# Output_Register.net
KiCad netlist of a schematic drawn in Altium Designer
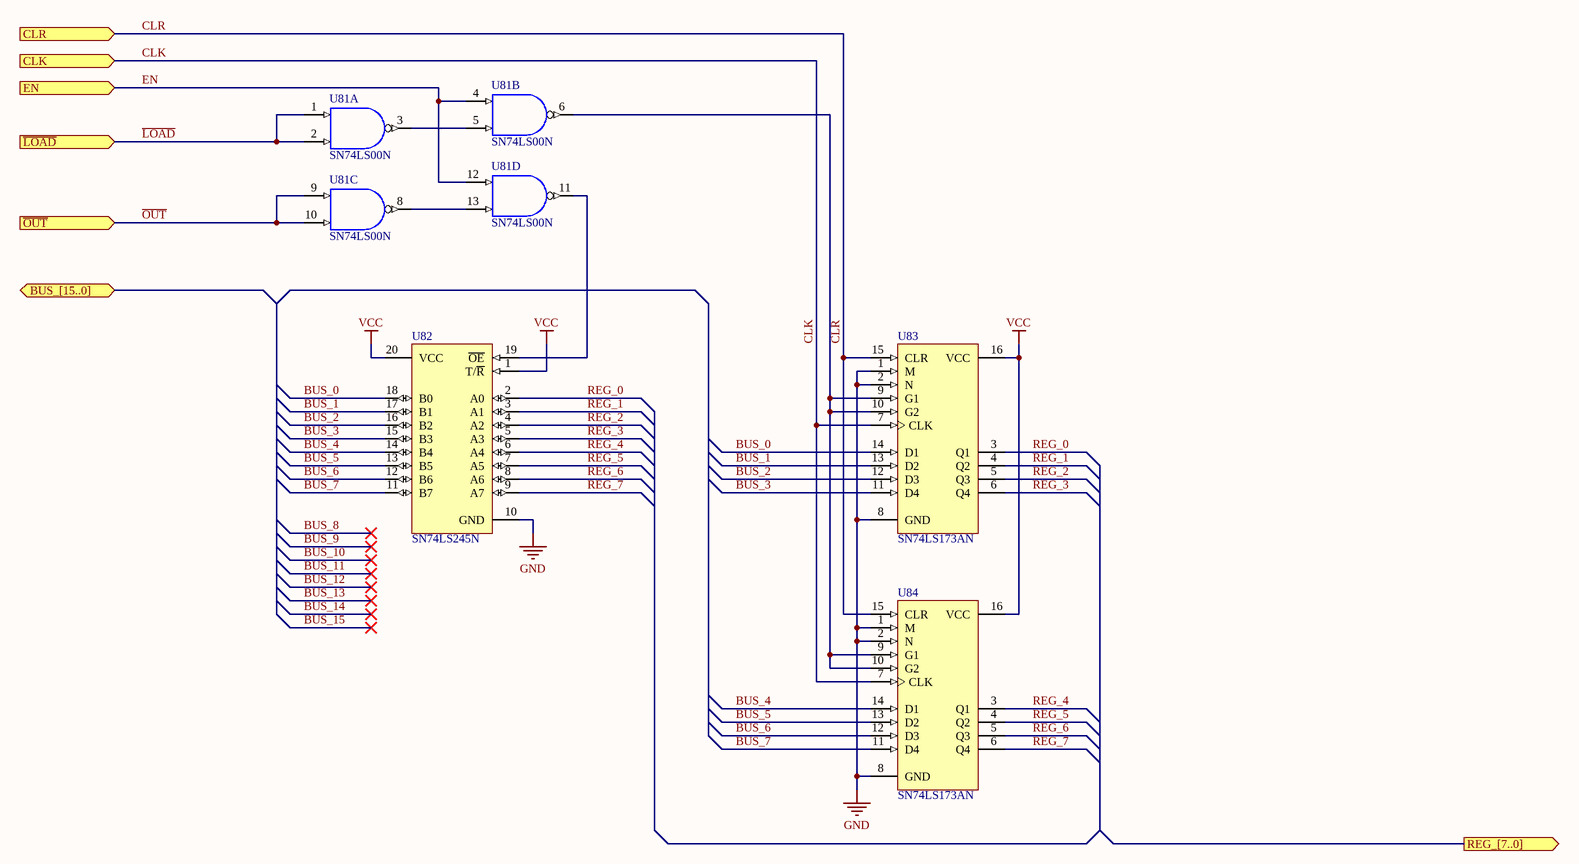
[diagram p0: Output_Register.SchDoc]

(export (version "E")
  (design (tool "Eeschema 10.0.6"))
  (components
    (comp (ref "U81")
      (value "SN74LS00N")
      (footprint "N014")
      (description "Quadruple 2-Input Positive-NAND Gate")
      (fields (field (name "PUBLISHER") "Altium Limited"))
      (libsource (lib "TI Logic Gate 2") (part "SN74LS00N"))
    )
    (comp (ref "U82")
      (value "SN74LS245N")
      (footprint "N020")
      (description "Octal Bus Transceiver with 3-State Outputs")
      (fields (field (name "PUBLISHER") "Altium Limited"))
      (libsource (lib "TI Interface 8-Bit Line Transceiver") (part "SN74LS245N"))
    )
    (comp (ref "U83")
      (value "SN74LS173AN")
      (footprint "N016D")
      (description "4-Bit D-Type Register with 3-State Outputs")
      (fields (field (name "PUBLISHER") "Altium Limited"))
      (libsource (lib "TI Logic Flip-Flop") (part "SN74LS173AN"))
    )
    (comp (ref "U84")
      (value "SN74LS173AN")
      (footprint "N016D")
      (description "4-Bit D-Type Register with 3-State Outputs")
      (fields (field (name "PUBLISHER") "Altium Limited"))
      (libsource (lib "TI Logic Flip-Flop") (part "SN74LS173AN"))
    )
  )
  (nets
    (net (code "1") (name "/BUS_0") (class "Default")
      (node (ref "U82") (pin "18") (pinfunction "B0_18") (pintype "bidirectional"))
      (node (ref "U83") (pin "14") (pinfunction "D1_14") (pintype "input"))
    )
    (net (code "2") (name "/BUS_1") (class "Default")
      (node (ref "U82") (pin "17") (pinfunction "B1_17") (pintype "bidirectional"))
      (node (ref "U83") (pin "13") (pinfunction "D2_13") (pintype "input"))
    )
    (net (code "3") (name "/BUS_2") (class "Default")
      (node (ref "U82") (pin "16") (pinfunction "B2_16") (pintype "bidirectional"))
      (node (ref "U83") (pin "12") (pinfunction "D3_12") (pintype "input"))
    )
    (net (code "4") (name "/BUS_3") (class "Default")
      (node (ref "U82") (pin "15") (pinfunction "B3_15") (pintype "bidirectional"))
      (node (ref "U83") (pin "11") (pinfunction "D4_11") (pintype "input"))
    )
    (net (code "5") (name "/BUS_4") (class "Default")
      (node (ref "U82") (pin "14") (pinfunction "B4_14") (pintype "bidirectional"))
      (node (ref "U84") (pin "14") (pinfunction "D1_14") (pintype "input"))
    )
    (net (code "6") (name "/BUS_5") (class "Default")
      (node (ref "U82") (pin "13") (pinfunction "B5_13") (pintype "bidirectional"))
      (node (ref "U84") (pin "13") (pinfunction "D2_13") (pintype "input"))
    )
    (net (code "7") (name "/BUS_6") (class "Default")
      (node (ref "U82") (pin "12") (pinfunction "B6_12") (pintype "bidirectional"))
      (node (ref "U84") (pin "12") (pinfunction "D3_12") (pintype "input"))
    )
    (net (code "8") (name "/BUS_7") (class "Default")
      (node (ref "U82") (pin "11") (pinfunction "B7_11") (pintype "bidirectional"))
      (node (ref "U84") (pin "11") (pinfunction "D4_11") (pintype "input"))
    )
    (net (code "18") (name "/CLK") (class "Default")
      (node (ref "U83") (pin "7") (pinfunction "CLK_7") (pintype "input"))
      (node (ref "U84") (pin "7") (pinfunction "CLK_7") (pintype "input"))
    )
    (net (code "19") (name "/CLR") (class "Default")
      (node (ref "U83") (pin "15") (pinfunction "CLR_15") (pintype "input"))
      (node (ref "U84") (pin "15") (pinfunction "CLR_15") (pintype "input"))
    )
    (net (code "20") (name "/EN") (class "Default")
      (node (ref "U81") (pin "12") (pinfunction "A_12") (pintype "input"))
      (node (ref "U81") (pin "4") (pinfunction "A_4") (pintype "input"))
    )
    (net (code "21") (name "/REG_0") (class "Default")
      (node (ref "U82") (pin "2") (pinfunction "A0_2") (pintype "bidirectional"))
      (node (ref "U83") (pin "3") (pinfunction "Q1_3") (pintype "tri_state"))
    )
    (net (code "22") (name "/REG_1") (class "Default")
      (node (ref "U82") (pin "3") (pinfunction "A1_3") (pintype "bidirectional"))
      (node (ref "U83") (pin "4") (pinfunction "Q2_4") (pintype "tri_state"))
    )
    (net (code "23") (name "/REG_2") (class "Default")
      (node (ref "U82") (pin "4") (pinfunction "A2_4") (pintype "bidirectional"))
      (node (ref "U83") (pin "5") (pinfunction "Q3_5") (pintype "tri_state"))
    )
    (net (code "24") (name "/REG_3") (class "Default")
      (node (ref "U82") (pin "5") (pinfunction "A3_5") (pintype "bidirectional"))
      (node (ref "U83") (pin "6") (pinfunction "Q4_6") (pintype "tri_state"))
    )
    (net (code "25") (name "/REG_4") (class "Default")
      (node (ref "U82") (pin "6") (pinfunction "A4_6") (pintype "bidirectional"))
      (node (ref "U84") (pin "3") (pinfunction "Q1_3") (pintype "tri_state"))
    )
    (net (code "26") (name "/REG_5") (class "Default")
      (node (ref "U82") (pin "7") (pinfunction "A5_7") (pintype "bidirectional"))
      (node (ref "U84") (pin "4") (pinfunction "Q2_4") (pintype "tri_state"))
    )
    (net (code "27") (name "/REG_6") (class "Default")
      (node (ref "U82") (pin "8") (pinfunction "A6_8") (pintype "bidirectional"))
      (node (ref "U84") (pin "5") (pinfunction "Q3_5") (pintype "tri_state"))
    )
    (net (code "28") (name "/REG_7") (class "Default")
      (node (ref "U82") (pin "9") (pinfunction "A7_9") (pintype "bidirectional"))
      (node (ref "U84") (pin "6") (pinfunction "Q4_6") (pintype "tri_state"))
    )
    (net (code "30") (name "/~{LOAD}") (class "Default")
      (node (ref "U81") (pin "1") (pinfunction "A_1") (pintype "input"))
      (node (ref "U81") (pin "2") (pinfunction "B_2") (pintype "input"))
    )
    (net (code "31") (name "/~{OUT}") (class "Default")
      (node (ref "U81") (pin "10") (pinfunction "B_10") (pintype "input"))
      (node (ref "U81") (pin "9") (pinfunction "A_9") (pintype "input"))
    )
    (net (code "32") (name "GND") (class "Default")
      (node (ref "U81") (pin "7") (pinfunction "GND_7") (pintype "power_in"))
      (node (ref "U82") (pin "10") (pinfunction "GND_10") (pintype "power_in"))
      (node (ref "U83") (pin "1") (pinfunction "M_1") (pintype "input"))
      (node (ref "U83") (pin "2") (pinfunction "N_2") (pintype "input"))
      (node (ref "U83") (pin "8") (pinfunction "GND_8") (pintype "power_in"))
      (node (ref "U84") (pin "1") (pinfunction "M_1") (pintype "input"))
      (node (ref "U84") (pin "2") (pinfunction "N_2") (pintype "input"))
      (node (ref "U84") (pin "8") (pinfunction "GND_8") (pintype "power_in"))
    )
    (net (code "33") (name "Net-(U81A-Y)") (class "Default")
      (node (ref "U81") (pin "3") (pinfunction "Y_3") (pintype "output"))
      (node (ref "U81") (pin "5") (pinfunction "B_5") (pintype "input"))
    )
    (net (code "34") (name "Net-(U81B-Y)") (class "Default")
      (node (ref "U81") (pin "6") (pinfunction "Y_6") (pintype "output"))
      (node (ref "U83") (pin "10") (pinfunction "G2_10") (pintype "input"))
      (node (ref "U83") (pin "9") (pinfunction "G1_9") (pintype "input"))
      (node (ref "U84") (pin "10") (pinfunction "G2_10") (pintype "input"))
      (node (ref "U84") (pin "9") (pinfunction "G1_9") (pintype "input"))
    )
    (net (code "35") (name "Net-(U81C-Y)") (class "Default")
      (node (ref "U81") (pin "13") (pinfunction "B_13") (pintype "input"))
      (node (ref "U81") (pin "8") (pinfunction "Y_8") (pintype "output"))
    )
    (net (code "36") (name "Net-(U81D-Y)") (class "Default")
      (node (ref "U81") (pin "11") (pinfunction "Y_11") (pintype "output"))
      (node (ref "U82") (pin "19") (pinfunction "~{OE}_19") (pintype "input"))
    )
    (net (code "37") (name "VCC") (class "Default")
      (node (ref "U81") (pin "14") (pinfunction "VCC_14") (pintype "power_in"))
      (node (ref "U82") (pin "1") (pinfunction "T/~{R}_1") (pintype "input"))
      (node (ref "U82") (pin "20") (pinfunction "VCC_20") (pintype "power_in"))
      (node (ref "U83") (pin "16") (pinfunction "VCC_16") (pintype "power_in"))
      (node (ref "U84") (pin "16") (pinfunction "VCC_16") (pintype "power_in"))
    )
  )
)
